# AudioCodec.net
KiCad netlist of a schematic drawn in Altium Designer
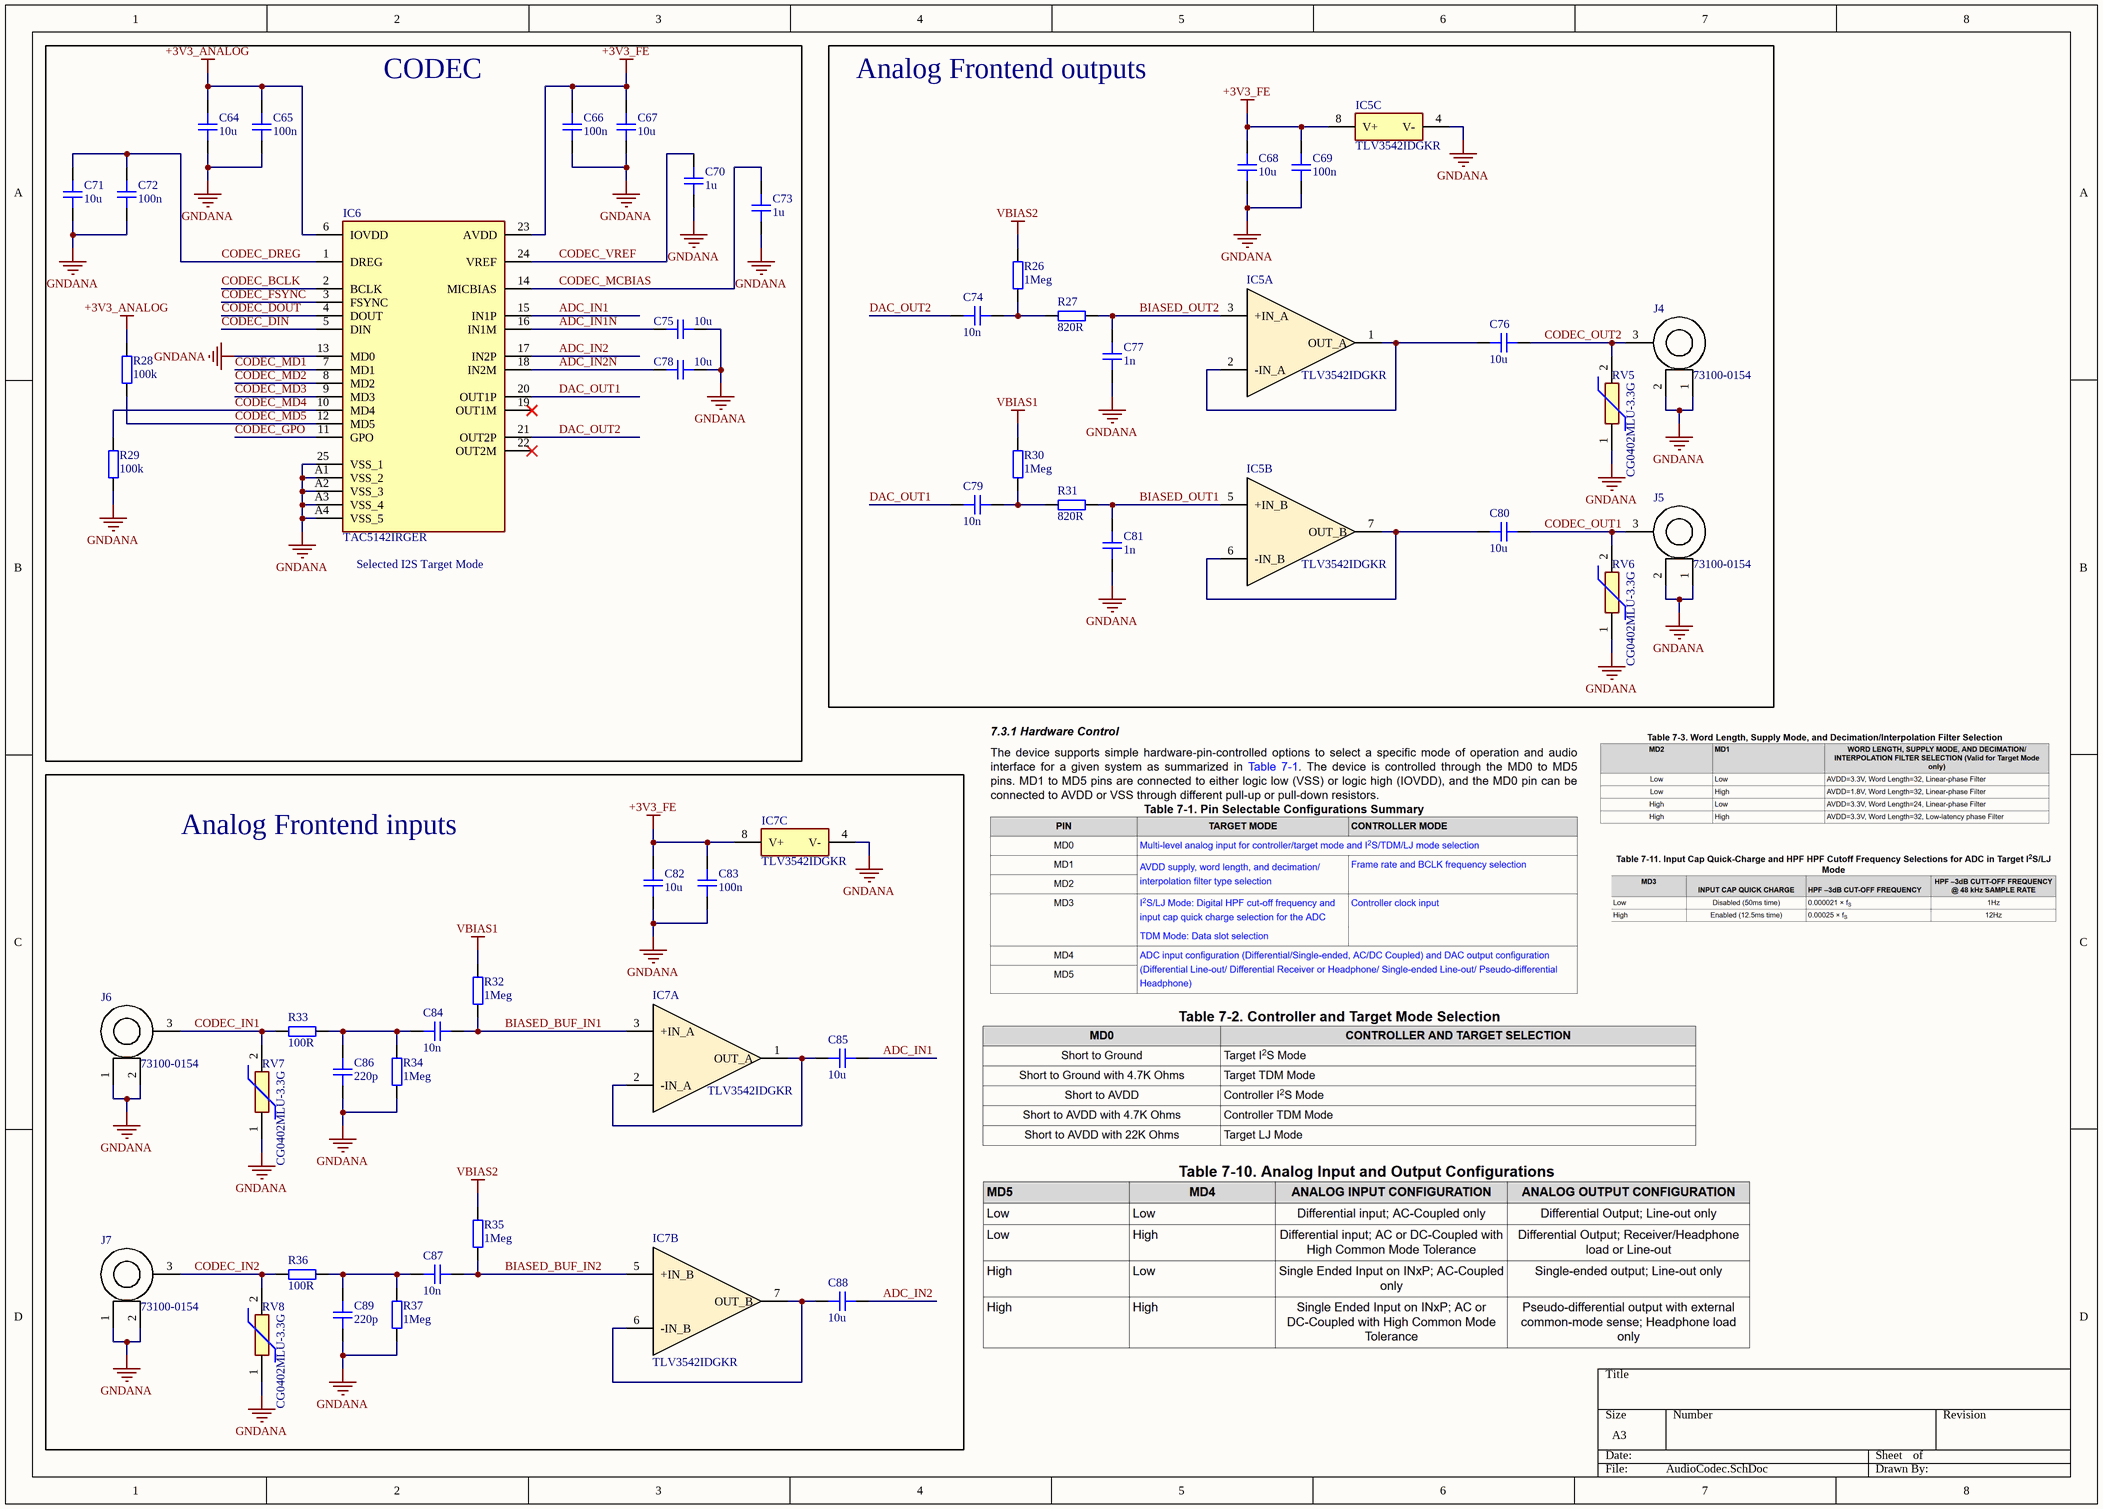
[diagram p0: AudioCodec.SchDoc]

(export (version "E")
  (design (tool "Eeschema 10.0.6"))
  (components
    (comp (ref "C64")
      (value "10u")
      (footprint "CAP_0603")
      (description "Capacitor SMD 0603")
      (libsource (lib "Schematic-Lib-PhilsLab") (part "CAP_0603"))
    )
    (comp (ref "C65")
      (value "100n")
      (footprint "CAP_0402")
      (description "Capacitor SMD 0402")
      (libsource (lib "Schematic-Lib-PhilsLab") (part "CAP_0402"))
    )
    (comp (ref "C66")
      (value "100n")
      (footprint "CAP_0402")
      (description "Capacitor SMD 0402")
      (libsource (lib "Schematic-Lib-PhilsLab") (part "CAP_0402"))
    )
    (comp (ref "C67")
      (value "10u")
      (footprint "CAP_0603")
      (description "Capacitor SMD 0603")
      (libsource (lib "Schematic-Lib-PhilsLab") (part "CAP_0603"))
    )
    (comp (ref "C68")
      (value "10u")
      (footprint "CAP_0603")
      (description "Capacitor SMD 0603")
      (libsource (lib "Schematic-Lib-PhilsLab") (part "CAP_0603"))
    )
    (comp (ref "C69")
      (value "100n")
      (footprint "CAP_0402")
      (description "Capacitor SMD 0402")
      (libsource (lib "Schematic-Lib-PhilsLab") (part "CAP_0402"))
    )
    (comp (ref "C70")
      (value "1u")
      (footprint "CAP_0402")
      (description "Capacitor SMD 0402")
      (libsource (lib "Schematic-Lib-PhilsLab") (part "CAP_0402"))
    )
    (comp (ref "C71")
      (value "10u")
      (footprint "CAP_0603")
      (description "Capacitor SMD 0603")
      (libsource (lib "Schematic-Lib-PhilsLab") (part "CAP_0603"))
    )
    (comp (ref "C72")
      (value "100n")
      (footprint "CAP_0402")
      (description "Capacitor SMD 0402")
      (libsource (lib "Schematic-Lib-PhilsLab") (part "CAP_0402"))
    )
    (comp (ref "C73")
      (value "1u")
      (footprint "CAP_0402")
      (description "Capacitor SMD 0402")
      (libsource (lib "Schematic-Lib-PhilsLab") (part "CAP_0402"))
    )
    (comp (ref "C74")
      (value "10n")
      (footprint "CAP_0402")
      (description "Capacitor SMD 0402")
      (libsource (lib "Schematic-Lib-PhilsLab") (part "CAP_0402"))
    )
    (comp (ref "C75")
      (value "10u")
      (footprint "CAP_0603")
      (description "Capacitor SMD 0603")
      (libsource (lib "Schematic-Lib-PhilsLab") (part "CAP_0603"))
    )
    (comp (ref "C76")
      (value "10u")
      (footprint "CAP_0603")
      (description "Capacitor SMD 0603")
      (libsource (lib "Schematic-Lib-PhilsLab") (part "CAP_0603"))
    )
    (comp (ref "C77")
      (value "1n")
      (footprint "CAP_0402")
      (description "Capacitor SMD 0402")
      (libsource (lib "Schematic-Lib-PhilsLab") (part "CAP_0402"))
    )
    (comp (ref "C78")
      (value "10u")
      (footprint "CAP_0603")
      (description "Capacitor SMD 0603")
      (libsource (lib "Schematic-Lib-PhilsLab") (part "CAP_0603"))
    )
    (comp (ref "C79")
      (value "10n")
      (footprint "CAP_0402")
      (description "Capacitor SMD 0402")
      (libsource (lib "Schematic-Lib-PhilsLab") (part "CAP_0402"))
    )
    (comp (ref "C80")
      (value "10u")
      (footprint "CAP_0603")
      (description "Capacitor SMD 0603")
      (libsource (lib "Schematic-Lib-PhilsLab") (part "CAP_0603"))
    )
    (comp (ref "C81")
      (value "1n")
      (footprint "CAP_0402")
      (description "Capacitor SMD 0402")
      (libsource (lib "Schematic-Lib-PhilsLab") (part "CAP_0402"))
    )
    (comp (ref "C82")
      (value "10u")
      (footprint "CAP_0603")
      (description "Capacitor SMD 0603")
      (libsource (lib "Schematic-Lib-PhilsLab") (part "CAP_0603"))
    )
    (comp (ref "C83")
      (value "100n")
      (footprint "CAP_0402")
      (description "Capacitor SMD 0402")
      (libsource (lib "Schematic-Lib-PhilsLab") (part "CAP_0402"))
    )
    (comp (ref "C84")
      (value "10n")
      (footprint "CAP_0402")
      (description "Capacitor SMD 0402")
      (libsource (lib "Schematic-Lib-PhilsLab") (part "CAP_0402"))
    )
    (comp (ref "C85")
      (value "10u")
      (footprint "CAP_0603")
      (description "Capacitor SMD 0603")
      (libsource (lib "Schematic-Lib-PhilsLab") (part "CAP_0603"))
    )
    (comp (ref "C86")
      (value "220p")
      (footprint "CAP_0402")
      (description "Capacitor SMD 0402")
      (libsource (lib "Schematic-Lib-PhilsLab") (part "CAP_0402"))
    )
    (comp (ref "C87")
      (value "10n")
      (footprint "CAP_0402")
      (description "Capacitor SMD 0402")
      (libsource (lib "Schematic-Lib-PhilsLab") (part "CAP_0402"))
    )
    (comp (ref "C88")
      (value "10u")
      (footprint "CAP_0603")
      (description "Capacitor SMD 0603")
      (libsource (lib "Schematic-Lib-PhilsLab") (part "CAP_0603"))
    )
    (comp (ref "C89")
      (value "220p")
      (footprint "CAP_0402")
      (description "Capacitor SMD 0402")
      (libsource (lib "Schematic-Lib-PhilsLab") (part "CAP_0402"))
    )
    (comp (ref "IC5")
      (value "TLV3542IDGKR")
      (footprint "Footprint-Lib-PhilsLab:SOP65P490X110-8N")
      (description "Integrated Circuit")
      (fields (field (name "MOUSER PART NUMBER") "595-TLV3542IDGKR"))
      (libsource (lib "Schematic-Lib-PhilsLab") (part "TLV3542IDGKR"))
    )
    (comp (ref "IC6")
      (value "TAC5142IRGER")
      (footprint "Footprint-Lib-PhilsLab:TAC5142IRGER")
      (description "Integrated Circuit")
      (libsource (lib "Schematic-Lib-PhilsLab") (part "TAC5142IRGER"))
    )
    (comp (ref "IC7")
      (value "TLV3542IDGKR")
      (footprint "Footprint-Lib-PhilsLab:SOP65P490X110-8N")
      (description "Integrated Circuit")
      (fields (field (name "MOUSER PART NUMBER") "595-TLV3542IDGKR"))
      (libsource (lib "Schematic-Lib-PhilsLab") (part "TLV3542IDGKR"))
    )
    (comp (ref "J4")
      (value "73100-0154")
      (footprint "Footprint-Lib-PhilsLab:73100-0105")
      (description "Connector")
      (fields
        (field (name "MANUFACTURER_PART_NUMBER") "73100-0105")
        (field (name "MOUSER PART NUMBER") "538-73100-0105")
      )
      (libsource (lib "Schematic-Lib-PhilsLab") (part "73100-0105"))
    )
    (comp (ref "J5")
      (value "73100-0154")
      (footprint "Footprint-Lib-PhilsLab:73100-0105")
      (description "Connector")
      (fields
        (field (name "MANUFACTURER_PART_NUMBER") "73100-0105")
        (field (name "MOUSER PART NUMBER") "538-73100-0105")
      )
      (libsource (lib "Schematic-Lib-PhilsLab") (part "73100-0105"))
    )
    (comp (ref "J6")
      (value "73100-0154")
      (footprint "Footprint-Lib-PhilsLab:73100-0105")
      (description "Connector")
      (fields
        (field (name "MANUFACTURER_PART_NUMBER") "73100-0105")
        (field (name "MOUSER PART NUMBER") "538-73100-0105")
      )
      (libsource (lib "Schematic-Lib-PhilsLab") (part "73100-0105"))
    )
    (comp (ref "J7")
      (value "73100-0154")
      (footprint "Footprint-Lib-PhilsLab:73100-0105")
      (description "Connector")
      (fields
        (field (name "MANUFACTURER_PART_NUMBER") "73100-0105")
        (field (name "MOUSER PART NUMBER") "538-73100-0105")
      )
      (libsource (lib "Schematic-Lib-PhilsLab") (part "73100-0105"))
    )
    (comp (ref "R26")
      (value "1Meg")
      (footprint "RES_0402")
      (description "Resistor SMD 0402")
      (libsource (lib "Schematic-Lib-PhilsLab") (part "RES_0402"))
    )
    (comp (ref "R27")
      (value "820R")
      (footprint "RES_0402")
      (description "Resistor SMD 0402")
      (libsource (lib "Schematic-Lib-PhilsLab") (part "RES_0402"))
    )
    (comp (ref "R28")
      (value "100k")
      (footprint "RES_0402")
      (description "Resistor SMD 0402")
      (libsource (lib "Schematic-Lib-PhilsLab") (part "RES_0402"))
    )
    (comp (ref "R29")
      (value "100k")
      (footprint "RES_0402")
      (description "Resistor SMD 0402")
      (libsource (lib "Schematic-Lib-PhilsLab") (part "RES_0402"))
    )
    (comp (ref "R30")
      (value "1Meg")
      (footprint "RES_0402")
      (description "Resistor SMD 0402")
      (libsource (lib "Schematic-Lib-PhilsLab") (part "RES_0402"))
    )
    (comp (ref "R31")
      (value "820R")
      (footprint "RES_0402")
      (description "Resistor SMD 0402")
      (libsource (lib "Schematic-Lib-PhilsLab") (part "RES_0402"))
    )
    (comp (ref "R32")
      (value "1Meg")
      (footprint "RES_0402")
      (description "Resistor SMD 0402")
      (libsource (lib "Schematic-Lib-PhilsLab") (part "RES_0402"))
    )
    (comp (ref "R33")
      (value "100R")
      (footprint "RES_0402")
      (description "Resistor SMD 0402")
      (libsource (lib "Schematic-Lib-PhilsLab") (part "RES_0402"))
    )
    (comp (ref "R34")
      (value "1Meg")
      (footprint "RES_0402")
      (description "Resistor SMD 0402")
      (libsource (lib "Schematic-Lib-PhilsLab") (part "RES_0402"))
    )
    (comp (ref "R35")
      (value "1Meg")
      (footprint "RES_0402")
      (description "Resistor SMD 0402")
      (libsource (lib "Schematic-Lib-PhilsLab") (part "RES_0402"))
    )
    (comp (ref "R36")
      (value "100R")
      (footprint "RES_0402")
      (description "Resistor SMD 0402")
      (libsource (lib "Schematic-Lib-PhilsLab") (part "RES_0402"))
    )
    (comp (ref "R37")
      (value "1Meg")
      (footprint "RES_0402")
      (description "Resistor SMD 0402")
      (libsource (lib "Schematic-Lib-PhilsLab") (part "RES_0402"))
    )
    (comp (ref "RV5")
      (value "CG0402MLU-3.3G")
      (footprint "Footprint-Lib-PhilsLab:VARC1005X41N")
      (description "ESD Diode")
      (fields (field (name "MOUSER PART NUMBER") "652-CG0402MLU-3.3G"))
      (libsource (lib "Schematic-Lib-PhilsLab") (part "CG0402MLU-3.3G"))
    )
    (comp (ref "RV6")
      (value "CG0402MLU-3.3G")
      (footprint "Footprint-Lib-PhilsLab:VARC1005X41N")
      (description "ESD Diode")
      (fields (field (name "MOUSER PART NUMBER") "652-CG0402MLU-3.3G"))
      (libsource (lib "Schematic-Lib-PhilsLab") (part "CG0402MLU-3.3G"))
    )
    (comp (ref "RV7")
      (value "CG0402MLU-3.3G")
      (footprint "Footprint-Lib-PhilsLab:VARC1005X41N")
      (description "ESD Diode")
      (fields (field (name "MOUSER PART NUMBER") "652-CG0402MLU-3.3G"))
      (libsource (lib "Schematic-Lib-PhilsLab") (part "CG0402MLU-3.3G"))
    )
    (comp (ref "RV8")
      (value "CG0402MLU-3.3G")
      (footprint "Footprint-Lib-PhilsLab:VARC1005X41N")
      (description "ESD Diode")
      (fields (field (name "MOUSER PART NUMBER") "652-CG0402MLU-3.3G"))
      (libsource (lib "Schematic-Lib-PhilsLab") (part "CG0402MLU-3.3G"))
    )
  )
  (nets
    (net (code "1") (name "+3V3_ANALOG") (class "Default")
      (node (ref "C64") (pin "2") (pinfunction "2_2") (pintype "passive"))
      (node (ref "C65") (pin "2") (pinfunction "2_2") (pintype "passive"))
      (node (ref "IC6") (pin "6") (pinfunction "IOVDD_6") (pintype "passive"))
      (node (ref "R28") (pin "2") (pinfunction "2_2") (pintype "passive"))
    )
    (net (code "2") (name "+3V3_FE") (class "Default")
      (node (ref "C66") (pin "2") (pinfunction "2_2") (pintype "passive"))
      (node (ref "C67") (pin "2") (pinfunction "2_2") (pintype "passive"))
      (node (ref "C68") (pin "2") (pinfunction "2_2") (pintype "passive"))
      (node (ref "C69") (pin "2") (pinfunction "2_2") (pintype "passive"))
      (node (ref "C82") (pin "2") (pinfunction "2_2") (pintype "passive"))
      (node (ref "C83") (pin "2") (pinfunction "2_2") (pintype "passive"))
      (node (ref "IC5") (pin "8") (pinfunction "V+_8") (pintype "passive"))
      (node (ref "IC6") (pin "23") (pinfunction "AVDD_23") (pintype "passive"))
      (node (ref "IC7") (pin "8") (pinfunction "V+_8") (pintype "passive"))
    )
    (net (code "3") (name "/ADC_IN1") (class "Default")
      (node (ref "C85") (pin "1") (pinfunction "1_1") (pintype "passive"))
      (node (ref "IC6") (pin "15") (pinfunction "IN1P_15") (pintype "passive"))
    )
    (net (code "4") (name "/ADC_IN1N") (class "Default")
      (node (ref "C75") (pin "2") (pinfunction "2_2") (pintype "passive"))
      (node (ref "IC6") (pin "16") (pinfunction "IN1M_16") (pintype "passive"))
    )
    (net (code "5") (name "/ADC_IN2") (class "Default")
      (node (ref "C88") (pin "1") (pinfunction "1_1") (pintype "passive"))
      (node (ref "IC6") (pin "17") (pinfunction "IN2P_17") (pintype "passive"))
    )
    (net (code "6") (name "/ADC_IN2N") (class "Default")
      (node (ref "C78") (pin "2") (pinfunction "2_2") (pintype "passive"))
      (node (ref "IC6") (pin "18") (pinfunction "IN2M_18") (pintype "passive"))
    )
    (net (code "7") (name "/BIASED_BUF_IN1") (class "Default")
      (node (ref "C84") (pin "1") (pinfunction "1_1") (pintype "passive"))
      (node (ref "IC7") (pin "3") (pinfunction "+IN_A_3") (pintype "passive"))
      (node (ref "R32") (pin "1") (pinfunction "1_1") (pintype "passive"))
    )
    (net (code "8") (name "/BIASED_BUF_IN2") (class "Default")
      (node (ref "C87") (pin "1") (pinfunction "1_1") (pintype "passive"))
      (node (ref "IC7") (pin "5") (pinfunction "+IN_B_5") (pintype "passive"))
      (node (ref "R35") (pin "1") (pinfunction "1_1") (pintype "passive"))
    )
    (net (code "9") (name "/BIASED_OUT1") (class "Default")
      (node (ref "C81") (pin "1") (pinfunction "1_1") (pintype "passive"))
      (node (ref "IC5") (pin "5") (pinfunction "+IN_B_5") (pintype "passive"))
      (node (ref "R31") (pin "1") (pinfunction "1_1") (pintype "passive"))
    )
    (net (code "10") (name "/BIASED_OUT2") (class "Default")
      (node (ref "C77") (pin "1") (pinfunction "1_1") (pintype "passive"))
      (node (ref "IC5") (pin "3") (pinfunction "+IN_A_3") (pintype "passive"))
      (node (ref "R27") (pin "1") (pinfunction "1_1") (pintype "passive"))
    )
    (net (code "11") (name "/CODEC_BCLK") (class "Default")
      (node (ref "IC6") (pin "2") (pinfunction "BCLK_2") (pintype "passive"))
    )
    (net (code "12") (name "/CODEC_DIN") (class "Default")
      (node (ref "IC6") (pin "5") (pinfunction "DIN_5") (pintype "passive"))
    )
    (net (code "13") (name "/CODEC_DOUT") (class "Default")
      (node (ref "IC6") (pin "4") (pinfunction "DOUT_4") (pintype "passive"))
    )
    (net (code "14") (name "/CODEC_DREG") (class "Default")
      (node (ref "C71") (pin "2") (pinfunction "2_2") (pintype "passive"))
      (node (ref "C72") (pin "2") (pinfunction "2_2") (pintype "passive"))
      (node (ref "IC6") (pin "1") (pinfunction "DREG_1") (pintype "passive"))
    )
    (net (code "15") (name "/CODEC_FSYNC") (class "Default")
      (node (ref "IC6") (pin "3") (pinfunction "FSYNC_3") (pintype "passive"))
    )
    (net (code "16") (name "/CODEC_GPO") (class "Default")
      (node (ref "IC6") (pin "11") (pinfunction "GPO_11") (pintype "passive"))
    )
    (net (code "17") (name "/CODEC_IN1") (class "Default")
      (node (ref "J6") (pin "3") (pintype "passive"))
      (node (ref "R33") (pin "2") (pinfunction "2_2") (pintype "passive"))
      (node (ref "RV7") (pin "2") (pinfunction "2_2") (pintype "passive"))
    )
    (net (code "18") (name "/CODEC_IN2") (class "Default")
      (node (ref "J7") (pin "3") (pintype "passive"))
      (node (ref "R36") (pin "2") (pinfunction "2_2") (pintype "passive"))
      (node (ref "RV8") (pin "2") (pinfunction "2_2") (pintype "passive"))
    )
    (net (code "19") (name "/CODEC_MCBIAS") (class "Default")
      (node (ref "C73") (pin "2") (pinfunction "2_2") (pintype "passive"))
      (node (ref "IC6") (pin "14") (pinfunction "MICBIAS_14") (pintype "passive"))
    )
    (net (code "20") (name "/CODEC_MD1") (class "Default")
      (node (ref "IC6") (pin "7") (pinfunction "MD1_7") (pintype "passive"))
    )
    (net (code "21") (name "/CODEC_MD2") (class "Default")
      (node (ref "IC6") (pin "8") (pinfunction "MD2_8") (pintype "passive"))
    )
    (net (code "22") (name "/CODEC_MD3") (class "Default")
      (node (ref "IC6") (pin "9") (pinfunction "MD3_9") (pintype "passive"))
    )
    (net (code "23") (name "/CODEC_MD4") (class "Default")
      (node (ref "IC6") (pin "10") (pinfunction "MD4_10") (pintype "passive"))
      (node (ref "R29") (pin "2") (pinfunction "2_2") (pintype "passive"))
    )
    (net (code "24") (name "/CODEC_MD5") (class "Default")
      (node (ref "IC6") (pin "12") (pinfunction "MD5_12") (pintype "passive"))
      (node (ref "R28") (pin "1") (pinfunction "1_1") (pintype "passive"))
    )
    (net (code "25") (name "/CODEC_OUT1") (class "Default")
      (node (ref "C80") (pin "1") (pinfunction "1_1") (pintype "passive"))
      (node (ref "J5") (pin "3") (pintype "passive"))
      (node (ref "RV6") (pin "2") (pinfunction "2_2") (pintype "passive"))
    )
    (net (code "26") (name "/CODEC_OUT2") (class "Default")
      (node (ref "C76") (pin "1") (pinfunction "1_1") (pintype "passive"))
      (node (ref "J4") (pin "3") (pintype "passive"))
      (node (ref "RV5") (pin "2") (pinfunction "2_2") (pintype "passive"))
    )
    (net (code "27") (name "/CODEC_VREF") (class "Default")
      (node (ref "C70") (pin "2") (pinfunction "2_2") (pintype "passive"))
      (node (ref "IC6") (pin "24") (pinfunction "VREF_24") (pintype "passive"))
    )
    (net (code "28") (name "/DAC_OUT1") (class "Default")
      (node (ref "C79") (pin "2") (pinfunction "2_2") (pintype "passive"))
      (node (ref "IC6") (pin "20") (pinfunction "OUT1P_20") (pintype "passive"))
    )
    (net (code "29") (name "/DAC_OUT2") (class "Default")
      (node (ref "C74") (pin "2") (pinfunction "2_2") (pintype "passive"))
      (node (ref "IC6") (pin "21") (pinfunction "OUT2P_21") (pintype "passive"))
    )
    (net (code "30") (name "GNDANA") (class "Default")
      (node (ref "C64") (pin "1") (pinfunction "1_1") (pintype "passive"))
      (node (ref "C65") (pin "1") (pinfunction "1_1") (pintype "passive"))
      (node (ref "C66") (pin "1") (pinfunction "1_1") (pintype "passive"))
      (node (ref "C67") (pin "1") (pinfunction "1_1") (pintype "passive"))
      (node (ref "C68") (pin "1") (pinfunction "1_1") (pintype "passive"))
      (node (ref "C69") (pin "1") (pinfunction "1_1") (pintype "passive"))
      (node (ref "C70") (pin "1") (pinfunction "1_1") (pintype "passive"))
      (node (ref "C71") (pin "1") (pinfunction "1_1") (pintype "passive"))
      (node (ref "C72") (pin "1") (pinfunction "1_1") (pintype "passive"))
      (node (ref "C73") (pin "1") (pinfunction "1_1") (pintype "passive"))
      (node (ref "C75") (pin "1") (pinfunction "1_1") (pintype "passive"))
      (node (ref "C77") (pin "2") (pinfunction "2_2") (pintype "passive"))
      (node (ref "C78") (pin "1") (pinfunction "1_1") (pintype "passive"))
      (node (ref "C81") (pin "2") (pinfunction "2_2") (pintype "passive"))
      (node (ref "C82") (pin "1") (pinfunction "1_1") (pintype "passive"))
      (node (ref "C83") (pin "1") (pinfunction "1_1") (pintype "passive"))
      (node (ref "C86") (pin "1") (pinfunction "1_1") (pintype "passive"))
      (node (ref "C89") (pin "1") (pinfunction "1_1") (pintype "passive"))
      (node (ref "IC5") (pin "4") (pinfunction "V-_4") (pintype "passive"))
      (node (ref "IC6") (pin "13") (pinfunction "MD0_13") (pintype "passive"))
      (node (ref "IC6") (pin "25") (pinfunction "VSS_1_25") (pintype "passive"))
      (node (ref "IC6") (pin "A1") (pinfunction "VSS_2_A1") (pintype "passive"))
      (node (ref "IC6") (pin "A2") (pinfunction "VSS_3_A2") (pintype "passive"))
      (node (ref "IC6") (pin "A3") (pinfunction "VSS_4_A3") (pintype "passive"))
      (node (ref "IC6") (pin "A4") (pinfunction "VSS_5_A4") (pintype "passive"))
      (node (ref "IC7") (pin "4") (pinfunction "V-_4") (pintype "passive"))
      (node (ref "J4") (pin "1") (pintype "passive"))
      (node (ref "J4") (pin "2") (pintype "passive"))
      (node (ref "J5") (pin "1") (pintype "passive"))
      (node (ref "J5") (pin "2") (pintype "passive"))
      (node (ref "J6") (pin "1") (pintype "passive"))
      (node (ref "J6") (pin "2") (pintype "passive"))
      (node (ref "J7") (pin "1") (pintype "passive"))
      (node (ref "J7") (pin "2") (pintype "passive"))
      (node (ref "R29") (pin "1") (pinfunction "1_1") (pintype "passive"))
      (node (ref "R34") (pin "1") (pinfunction "1_1") (pintype "passive"))
      (node (ref "R37") (pin "1") (pinfunction "1_1") (pintype "passive"))
      (node (ref "RV5") (pin "1") (pinfunction "1_1") (pintype "passive"))
      (node (ref "RV6") (pin "1") (pinfunction "1_1") (pintype "passive"))
      (node (ref "RV7") (pin "1") (pinfunction "1_1") (pintype "passive"))
      (node (ref "RV8") (pin "1") (pinfunction "1_1") (pintype "passive"))
    )
    (net (code "31") (name "Net-(C74-Pad1)") (class "Default")
      (node (ref "C74") (pin "1") (pinfunction "1_1") (pintype "passive"))
      (node (ref "R26") (pin "1") (pinfunction "1_1") (pintype "passive"))
      (node (ref "R27") (pin "2") (pinfunction "2_2") (pintype "passive"))
    )
    (net (code "32") (name "Net-(C79-Pad1)") (class "Default")
      (node (ref "C79") (pin "1") (pinfunction "1_1") (pintype "passive"))
      (node (ref "R30") (pin "1") (pinfunction "1_1") (pintype "passive"))
      (node (ref "R31") (pin "2") (pinfunction "2_2") (pintype "passive"))
    )
    (net (code "33") (name "Net-(C84-Pad2)") (class "Default")
      (node (ref "C84") (pin "2") (pinfunction "2_2") (pintype "passive"))
      (node (ref "C86") (pin "2") (pinfunction "2_2") (pintype "passive"))
      (node (ref "R33") (pin "1") (pinfunction "1_1") (pintype "passive"))
      (node (ref "R34") (pin "2") (pinfunction "2_2") (pintype "passive"))
    )
    (net (code "34") (name "Net-(C87-Pad2)") (class "Default")
      (node (ref "C87") (pin "2") (pinfunction "2_2") (pintype "passive"))
      (node (ref "C89") (pin "2") (pinfunction "2_2") (pintype "passive"))
      (node (ref "R36") (pin "1") (pinfunction "1_1") (pintype "passive"))
      (node (ref "R37") (pin "2") (pinfunction "2_2") (pintype "passive"))
    )
    (net (code "35") (name "Net-(IC5A--IN_A)") (class "Default")
      (node (ref "C76") (pin "2") (pinfunction "2_2") (pintype "passive"))
      (node (ref "IC5") (pin "1") (pinfunction "OUT_A_1") (pintype "passive"))
      (node (ref "IC5") (pin "2") (pinfunction "-IN_A_2") (pintype "passive"))
    )
    (net (code "36") (name "Net-(IC5B--IN_B)") (class "Default")
      (node (ref "C80") (pin "2") (pinfunction "2_2") (pintype "passive"))
      (node (ref "IC5") (pin "6") (pinfunction "-IN_B_6") (pintype "passive"))
      (node (ref "IC5") (pin "7") (pinfunction "OUT_B_7") (pintype "passive"))
    )
    (net (code "37") (name "Net-(IC7A--IN_A)") (class "Default")
      (node (ref "C85") (pin "2") (pinfunction "2_2") (pintype "passive"))
      (node (ref "IC7") (pin "1") (pinfunction "OUT_A_1") (pintype "passive"))
      (node (ref "IC7") (pin "2") (pinfunction "-IN_A_2") (pintype "passive"))
    )
    (net (code "38") (name "Net-(IC7B--IN_B)") (class "Default")
      (node (ref "C88") (pin "2") (pinfunction "2_2") (pintype "passive"))
      (node (ref "IC7") (pin "6") (pinfunction "-IN_B_6") (pintype "passive"))
      (node (ref "IC7") (pin "7") (pinfunction "OUT_B_7") (pintype "passive"))
    )
    (net (code "39") (name "VBIAS1") (class "Default")
      (node (ref "R30") (pin "2") (pinfunction "2_2") (pintype "passive"))
      (node (ref "R32") (pin "2") (pinfunction "2_2") (pintype "passive"))
    )
    (net (code "40") (name "VBIAS2") (class "Default")
      (node (ref "R26") (pin "2") (pinfunction "2_2") (pintype "passive"))
      (node (ref "R35") (pin "2") (pinfunction "2_2") (pintype "passive"))
    )
    (net (code "41") (name "unconnected-(IC6-OUT1M-Pad19)") (class "Default")
      (node (ref "IC6") (pin "19") (pinfunction "OUT1M_19") (pintype "passive+no_connect"))
    )
    (net (code "42") (name "unconnected-(IC6-OUT2M-Pad22)") (class "Default")
      (node (ref "IC6") (pin "22") (pinfunction "OUT2M_22") (pintype "passive+no_connect"))
    )
  )
)
